# gate.net
KiCad netlist of a schematic drawn in EAGLE
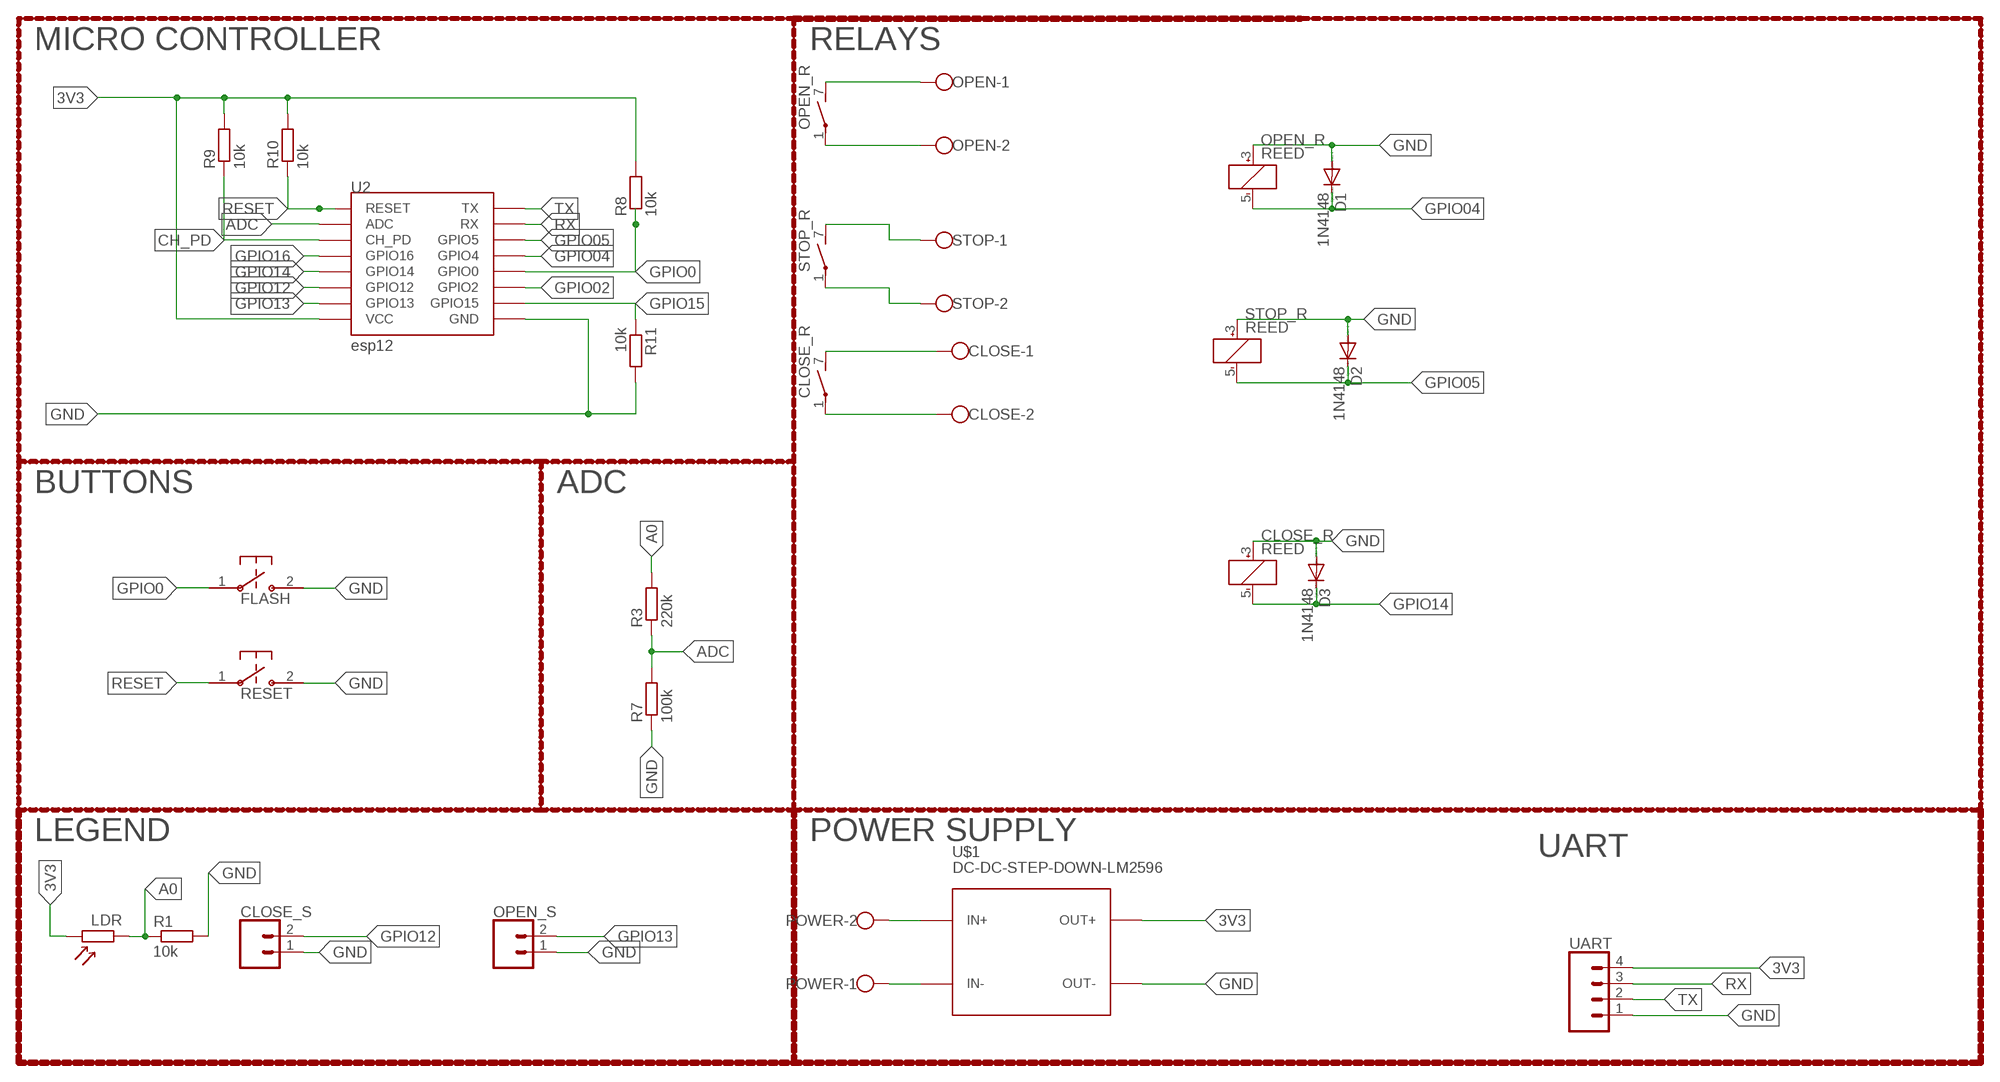
[diagram p0: schematic, sheet 1]

(export (version "E")
  (design (tool "Eeschema 10.0.6"))
  (components
    (comp (ref "CLOSE")
      (value "W237-102")
      (footprint "eagle-import:W237-102")
      (fields (field (name "MPN") "237-102"))
      (libsource (lib "eagle-import") (part "W237-102"))
    )
    (comp (ref "CLOSE_R")
      (value "REED")
      (footprint "eagle-import:REED")
      (libsource (lib "eagle-import") (part "REED"))
    )
    (comp (ref "CLOSE_S")
      (value "CONN_023.5MM")
      (footprint "eagle-import:SCREWTERMINAL-3.5MM-2")
      (libsource (lib "eagle-import") (part "CONN_023.5MM"))
    )
    (comp (ref "D1")
      (value "1N4148")
      (footprint "eagle-import:SOD80C")
      (libsource (lib "eagle-import") (part "DIODE-SOD80C"))
    )
    (comp (ref "D2")
      (value "1N4148")
      (footprint "eagle-import:SOD80C")
      (libsource (lib "eagle-import") (part "DIODE-SOD80C"))
    )
    (comp (ref "D3")
      (value "1N4148")
      (footprint "eagle-import:SOD80C")
      (libsource (lib "eagle-import") (part "DIODE-SOD80C"))
    )
    (comp (ref "FLASH")
      (value "B3U-1000P-2P-SMD")
      (footprint "eagle-import:B3U-1000P")
      (fields
        (field (name "MANUFACTURER") "Omron")
        (field (name "MPN") "B3U-1000P")
        (field (name "SPICEPREFIX") "F")
      )
      (libsource (lib "eagle-import") (part "B3U-1000P"))
    )
    (comp (ref "LDR")
      (value "LDR-TH")
      (footprint "eagle-import:1X02")
      (libsource (lib "eagle-import") (part "LDR-TH"))
    )
    (comp (ref "OPEN")
      (value "W237-102")
      (footprint "eagle-import:W237-102")
      (fields (field (name "MPN") "237-102"))
      (libsource (lib "eagle-import") (part "W237-102"))
    )
    (comp (ref "OPEN_R")
      (value "REED")
      (footprint "eagle-import:REED")
      (libsource (lib "eagle-import") (part "REED"))
    )
    (comp (ref "OPEN_S")
      (value "CONN_023.5MM")
      (footprint "eagle-import:SCREWTERMINAL-3.5MM-2")
      (libsource (lib "eagle-import") (part "CONN_023.5MM"))
    )
    (comp (ref "POWER")
      (value "W237-102")
      (footprint "eagle-import:W237-102")
      (fields (field (name "MPN") "237-102"))
      (libsource (lib "eagle-import") (part "W237-102"))
    )
    (comp (ref "R1")
      (value "10k")
      (footprint "eagle-import:R0603")
      (libsource (lib "eagle-import") (part "R-EU_R0603"))
    )
    (comp (ref "R3")
      (value "220k")
      (footprint "eagle-import:R0603")
      (libsource (lib "eagle-import") (part "R-EU_R0603"))
    )
    (comp (ref "R7")
      (value "100k")
      (footprint "eagle-import:R0603")
      (libsource (lib "eagle-import") (part "R-EU_R0603"))
    )
    (comp (ref "R8")
      (value "10k")
      (footprint "eagle-import:R0603")
      (libsource (lib "eagle-import") (part "R-EU_R0603"))
    )
    (comp (ref "R9")
      (value "10k")
      (footprint "eagle-import:R0603")
      (libsource (lib "eagle-import") (part "R-EU_R0603"))
    )
    (comp (ref "R10")
      (value "10k")
      (footprint "eagle-import:R0603")
      (libsource (lib "eagle-import") (part "R-EU_R0603"))
    )
    (comp (ref "R11")
      (value "10k")
      (footprint "eagle-import:R0603")
      (libsource (lib "eagle-import") (part "R-EU_R0603"))
    )
    (comp (ref "RESET")
      (value "B3U-1000P-2P-SMD")
      (footprint "eagle-import:B3U-1000P")
      (fields (field (name "MANUFACTURER") "Omron") (field (name "MPN") "B3U-1000P"))
      (libsource (lib "eagle-import") (part "B3U-1000P"))
    )
    (comp (ref "STOP")
      (value "W237-102")
      (footprint "eagle-import:W237-102")
      (fields (field (name "MPN") "237-102"))
      (libsource (lib "eagle-import") (part "W237-102"))
    )
    (comp (ref "STOP_R")
      (value "REED")
      (footprint "eagle-import:REED")
      (libsource (lib "eagle-import") (part "REED"))
    )
    (comp (ref "U$1")
      (value "DC-DC-STEP-DOWN-LM2596")
      (footprint "eagle-import:DC-DC-STEP-DOWN-LM2596")
      (libsource (lib "eagle-import") (part "DC-DC-STEP-DOWN-LM2596"))
    )
    (comp (ref "U2")
      (value "esp12")
      (footprint "eagle-import:ESP12-SMD")
      (libsource (lib "eagle-import") (part "ESP12SMD"))
    )
    (comp (ref "UART")
      (value "CONN_04SCREW")
      (footprint "eagle-import:SCREWTERMINAL-3.5MM-4")
      (libsource (lib "eagle-import") (part "CONN_04SCREW"))
    )
  )
  (nets
    (net (code "1") (name "3V3") (class "Default")
      (node (ref "LDR") (pin "2") (pinfunction "2_2") (pintype "passive"))
      (node (ref "R10") (pin "2") (pinfunction "2_2") (pintype "passive"))
      (node (ref "R8") (pin "2") (pinfunction "2_2") (pintype "passive"))
      (node (ref "R9") (pin "2") (pinfunction "2_2") (pintype "passive"))
      (node (ref "U$1") (pin "OUT+") (pinfunction "OUT+_OUT+") (pintype "bidirectional"))
      (node (ref "U2") (pin "VCC") (pinfunction "VCC_VCC") (pintype "bidirectional"))
      (node (ref "UART") (pin "4") (pinfunction "4_4") (pintype "passive"))
    )
    (net (code "2") (name "A0") (class "Default")
      (node (ref "LDR") (pin "1") (pinfunction "1_1") (pintype "passive"))
      (node (ref "R1") (pin "1") (pinfunction "1_1") (pintype "passive"))
      (node (ref "R3") (pin "2") (pinfunction "2_2") (pintype "passive"))
    )
    (net (code "3") (name "ADC") (class "Default")
      (node (ref "R3") (pin "1") (pinfunction "1_1") (pintype "passive"))
      (node (ref "R7") (pin "2") (pinfunction "2_2") (pintype "passive"))
      (node (ref "U2") (pin "ADC") (pinfunction "ADC_ADC") (pintype "bidirectional"))
    )
    (net (code "4") (name "CH_PD") (class "Default")
      (node (ref "R9") (pin "1") (pinfunction "1_1") (pintype "passive"))
      (node (ref "U2") (pin "CH_PD") (pinfunction "CH_PD_CH_PD") (pintype "bidirectional"))
    )
    (net (code "5") (name "GND") (class "Default")
      (node (ref "CLOSE_R") (pin "3") (pinfunction "+_3") (pintype "passive"))
      (node (ref "CLOSE_S") (pin "1") (pinfunction "1_1") (pintype "passive"))
      (node (ref "D1") (pin "A") (pinfunction "A_A") (pintype "passive"))
      (node (ref "D2") (pin "A") (pinfunction "A_A") (pintype "passive"))
      (node (ref "D3") (pin "A") (pinfunction "A_A") (pintype "passive"))
      (node (ref "FLASH") (pin "2") (pinfunction "P$2_2") (pintype "passive"))
      (node (ref "OPEN_R") (pin "3") (pinfunction "+_3") (pintype "passive"))
      (node (ref "OPEN_S") (pin "1") (pinfunction "1_1") (pintype "passive"))
      (node (ref "POWER") (pin "1") (pinfunction "KL_1") (pintype "passive"))
      (node (ref "R1") (pin "2") (pinfunction "2_2") (pintype "passive"))
      (node (ref "R11") (pin "2") (pinfunction "2_2") (pintype "passive"))
      (node (ref "R7") (pin "1") (pinfunction "1_1") (pintype "passive"))
      (node (ref "RESET") (pin "2") (pinfunction "P$2_2") (pintype "passive"))
      (node (ref "STOP_R") (pin "3") (pinfunction "+_3") (pintype "passive"))
      (node (ref "U$1") (pin "IN-") (pinfunction "IN-_IN-") (pintype "bidirectional"))
      (node (ref "U$1") (pin "OUT-") (pinfunction "OUT-_OUT-") (pintype "bidirectional"))
      (node (ref "U2") (pin "GND") (pinfunction "GND_GND") (pintype "bidirectional"))
      (node (ref "UART") (pin "1") (pinfunction "1_1") (pintype "passive"))
    )
    (net (code "6") (name "GPIO0") (class "Default")
      (node (ref "FLASH") (pin "1") (pinfunction "P$1_1") (pintype "passive"))
      (node (ref "R8") (pin "1") (pinfunction "1_1") (pintype "passive"))
      (node (ref "U2") (pin "GPIO0") (pinfunction "GPIO0_GPIO0") (pintype "bidirectional"))
    )
    (net (code "7") (name "GPIO02") (class "Default")
      (node (ref "U2") (pin "GPIO2") (pinfunction "GPIO2_GPIO2") (pintype "bidirectional"))
    )
    (net (code "8") (name "GPIO04") (class "Default")
      (node (ref "D1") (pin "C") (pinfunction "C_C") (pintype "passive"))
      (node (ref "OPEN_R") (pin "5") (pinfunction "-_5") (pintype "passive"))
      (node (ref "U2") (pin "GPIO4") (pinfunction "GPIO4_GPIO4") (pintype "bidirectional"))
    )
    (net (code "9") (name "GPIO05") (class "Default")
      (node (ref "D2") (pin "C") (pinfunction "C_C") (pintype "passive"))
      (node (ref "STOP_R") (pin "5") (pinfunction "-_5") (pintype "passive"))
      (node (ref "U2") (pin "GPIO5") (pinfunction "GPIO5_GPIO5") (pintype "bidirectional"))
    )
    (net (code "10") (name "GPIO12") (class "Default")
      (node (ref "CLOSE_S") (pin "2") (pinfunction "2_2") (pintype "passive"))
      (node (ref "U2") (pin "GPIO12") (pinfunction "GPIO12_GPIO12") (pintype "bidirectional"))
    )
    (net (code "11") (name "GPIO13") (class "Default")
      (node (ref "OPEN_S") (pin "2") (pinfunction "2_2") (pintype "passive"))
      (node (ref "U2") (pin "GPIO13") (pinfunction "GPIO13_GPIO13") (pintype "bidirectional"))
    )
    (net (code "12") (name "GPIO14") (class "Default")
      (node (ref "CLOSE_R") (pin "5") (pinfunction "-_5") (pintype "passive"))
      (node (ref "D3") (pin "C") (pinfunction "C_C") (pintype "passive"))
      (node (ref "U2") (pin "GPIO14") (pinfunction "GPIO14_GPIO14") (pintype "bidirectional"))
    )
    (net (code "13") (name "GPIO15") (class "Default")
      (node (ref "R11") (pin "1") (pinfunction "1_1") (pintype "passive"))
      (node (ref "U2") (pin "GPIO15") (pinfunction "GPIO15_GPIO15") (pintype "bidirectional"))
    )
    (net (code "14") (name "GPIO16") (class "Default")
      (node (ref "U2") (pin "GPIO16") (pinfunction "GPIO16_GPIO16") (pintype "bidirectional"))
    )
    (net (code "15") (name "Net-(CLOSEA-KL)") (class "Default")
      (node (ref "CLOSE") (pin "1") (pinfunction "KL_1") (pintype "passive"))
      (node (ref "CLOSE_R") (pin "7") (pinfunction "S_7") (pintype "passive"))
    )
    (net (code "16") (name "Net-(CLOSEB-KL)") (class "Default")
      (node (ref "CLOSE") (pin "2") (pinfunction "KL_2") (pintype "passive"))
      (node (ref "CLOSE_R") (pin "1") (pinfunction "P_1") (pintype "passive"))
    )
    (net (code "17") (name "Net-(OPENA-KL)") (class "Default")
      (node (ref "OPEN") (pin "1") (pinfunction "KL_1") (pintype "passive"))
      (node (ref "OPEN_R") (pin "7") (pinfunction "S_7") (pintype "passive"))
    )
    (net (code "18") (name "Net-(OPENB-KL)") (class "Default")
      (node (ref "OPEN") (pin "2") (pinfunction "KL_2") (pintype "passive"))
      (node (ref "OPEN_R") (pin "1") (pinfunction "P_1") (pintype "passive"))
    )
    (net (code "19") (name "Net-(POWERB-KL)") (class "Default")
      (node (ref "POWER") (pin "2") (pinfunction "KL_2") (pintype "passive"))
      (node (ref "U$1") (pin "IN+") (pinfunction "IN+_IN+") (pintype "bidirectional"))
    )
    (net (code "20") (name "Net-(STOPA-KL)") (class "Default")
      (node (ref "STOP") (pin "1") (pinfunction "KL_1") (pintype "passive"))
      (node (ref "STOP_R") (pin "7") (pinfunction "S_7") (pintype "passive"))
    )
    (net (code "21") (name "Net-(STOPB-KL)") (class "Default")
      (node (ref "STOP") (pin "2") (pinfunction "KL_2") (pintype "passive"))
      (node (ref "STOP_R") (pin "1") (pinfunction "P_1") (pintype "passive"))
    )
    (net (code "22") (name "RESET") (class "Default")
      (node (ref "R10") (pin "1") (pinfunction "1_1") (pintype "passive"))
      (node (ref "RESET") (pin "1") (pinfunction "P$1_1") (pintype "passive"))
      (node (ref "U2") (pin "RESET") (pinfunction "RESET_RESET") (pintype "bidirectional"))
    )
    (net (code "23") (name "RX") (class "Default")
      (node (ref "U2") (pin "RXD0") (pinfunction "RX_RXD0") (pintype "bidirectional"))
      (node (ref "UART") (pin "3") (pinfunction "3_3") (pintype "passive"))
    )
    (net (code "24") (name "TX") (class "Default")
      (node (ref "U2") (pin "TXD0") (pinfunction "TX_TXD0") (pintype "bidirectional"))
      (node (ref "UART") (pin "2") (pinfunction "2_2") (pintype "passive"))
    )
  )
)
